# LEDs.net
KiCad netlist of a schematic drawn in Altium Designer
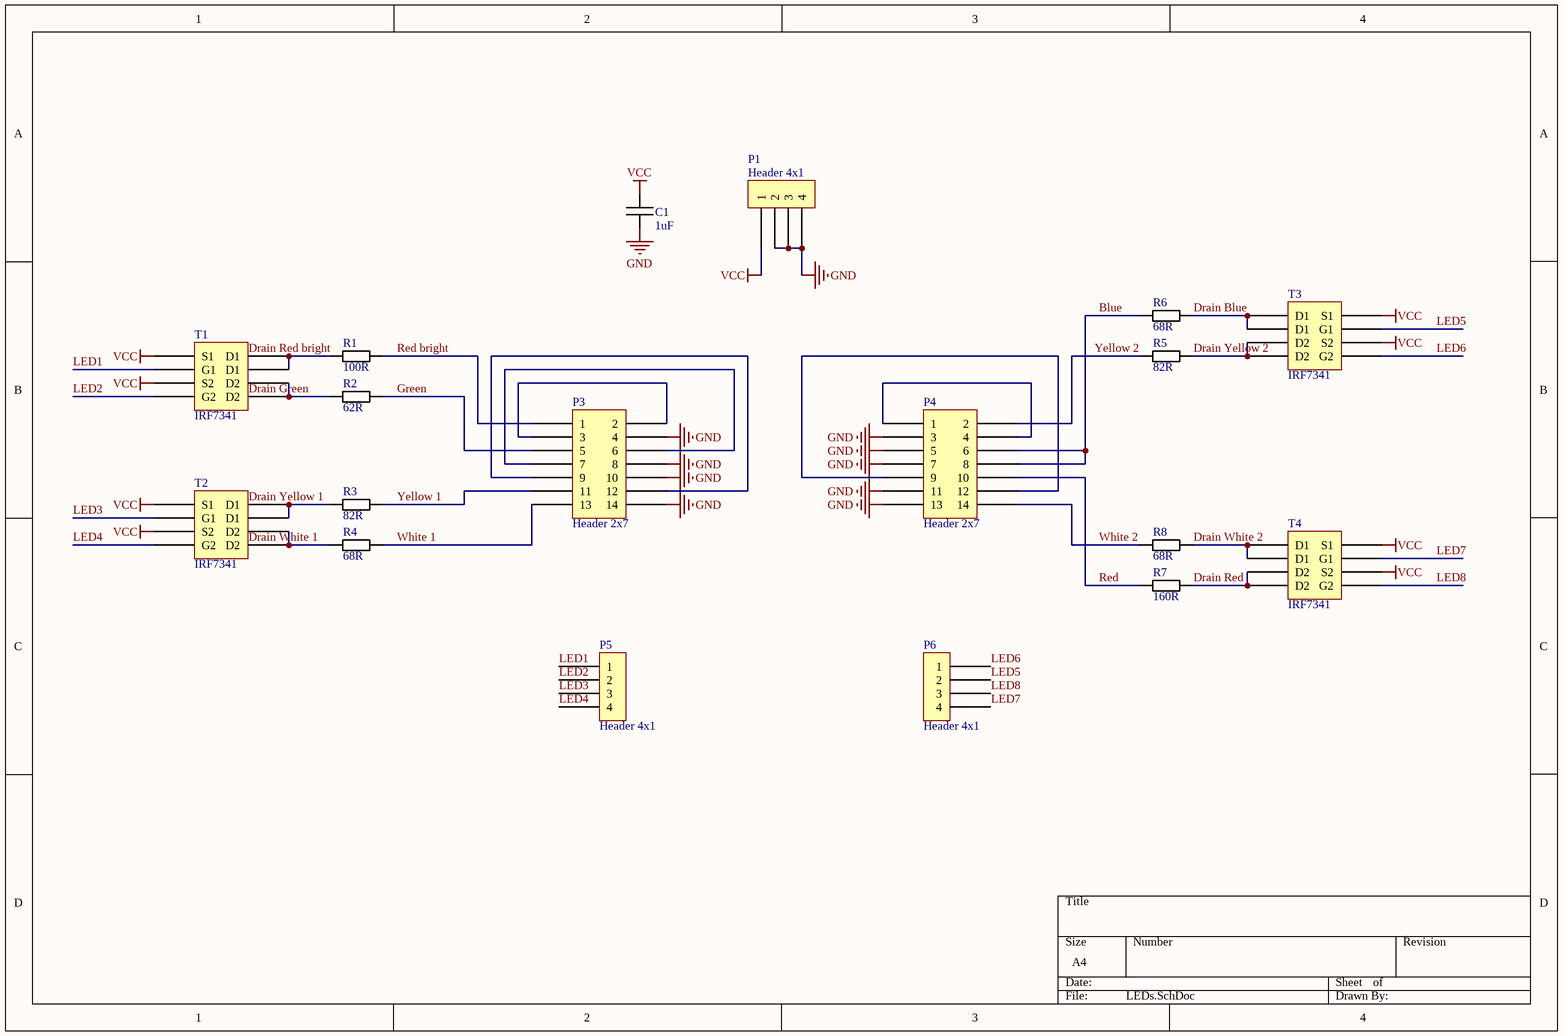
[diagram p0: LEDs.SchDoc]

(export (version "E")
  (design (tool "Eeschema 10.0.6"))
  (components
    (comp (ref "C1") (value "1uF") (footprint "C 0805 / 2012") (libsource (lib "LEDs") (part "Capacitor")))
    (comp (ref "P1")
      (value "Header 4x1")
      (footprint "Header 4x1 2.54mm")
      (libsource (lib "") (part "Header 4x1_1"))
    )
    (comp (ref "P3")
      (value "Header 2x7")
      (footprint "Header 7x2 2.54mm")
      (libsource (lib "LEDs") (part "Header 2x7"))
    )
    (comp (ref "P4")
      (value "Header 2x7")
      (footprint "Header 7x2 2.54mm")
      (libsource (lib "LEDs") (part "Header 2x7"))
    )
    (comp (ref "P5")
      (value "Header 4x1")
      (footprint "Header 4x1 2.54mm")
      (libsource (lib "LEDs") (part "Header 4x1"))
    )
    (comp (ref "P6")
      (value "Header 4x1")
      (footprint "Header 4x1 2.54mm")
      (libsource (lib "") (part "Header 4x1_2"))
    )
    (comp (ref "R1")
      (value "100R")
      (footprint "R 0805 / 2012")
      (description "Resistor")
      (libsource (lib "LEDs") (part "Resistor"))
    )
    (comp (ref "R2")
      (value "62R")
      (footprint "R 0805 / 2012")
      (description "Resistor")
      (libsource (lib "LEDs") (part "Resistor"))
    )
    (comp (ref "R3")
      (value "82R")
      (footprint "R 0805 / 2012")
      (description "Resistor")
      (libsource (lib "LEDs") (part "Resistor"))
    )
    (comp (ref "R4")
      (value "68R")
      (footprint "R 0805 / 2012")
      (description "Resistor")
      (libsource (lib "LEDs") (part "Resistor"))
    )
    (comp (ref "R5")
      (value "82R")
      (footprint "R 0805 / 2012")
      (description "Resistor")
      (libsource (lib "LEDs") (part "Resistor"))
    )
    (comp (ref "R6")
      (value "68R")
      (footprint "R 0805 / 2012")
      (description "Resistor")
      (libsource (lib "LEDs") (part "Resistor"))
    )
    (comp (ref "R7")
      (value "160R")
      (footprint "R 0805 / 2012")
      (description "Resistor")
      (libsource (lib "LEDs") (part "Resistor"))
    )
    (comp (ref "R8")
      (value "68R")
      (footprint "R 0805 / 2012")
      (description "Resistor")
      (libsource (lib "LEDs") (part "Resistor"))
    )
    (comp (ref "T1") (value "IRF7341") (footprint "SOIC8") (libsource (lib "") (part "IRF7341_1")))
    (comp (ref "T2") (value "IRF7341") (footprint "SOIC8") (libsource (lib "") (part "IRF7341_1")))
    (comp (ref "T3") (value "IRF7341") (footprint "SOIC8") (libsource (lib "LEDs") (part "IRF7341")))
    (comp (ref "T4") (value "IRF7341") (footprint "SOIC8") (libsource (lib "LEDs") (part "IRF7341")))
  )
  (nets
    (net (code "1") (name "/Blue") (class "Default")
      (node (ref "P4") (pin "6") (pinfunction "6_6") (pintype "passive"))
      (node (ref "P4") (pin "8") (pinfunction "8_8") (pintype "passive"))
      (node (ref "R6") (pin "1") (pinfunction "1_1") (pintype "passive"))
    )
    (net (code "2") (name "/Drain Blue") (class "Default")
      (node (ref "R6") (pin "2") (pinfunction "2_2") (pintype "passive"))
      (node (ref "T3") (pin "7") (pinfunction "D1_7") (pintype "passive"))
      (node (ref "T3") (pin "8") (pinfunction "D1_8") (pintype "passive"))
    )
    (net (code "4") (name "/Drain Red") (class "Default")
      (node (ref "R7") (pin "2") (pinfunction "2_2") (pintype "passive"))
      (node (ref "T4") (pin "5") (pinfunction "D2_5") (pintype "passive"))
      (node (ref "T4") (pin "6") (pinfunction "D2_6") (pintype "passive"))
    )
    (net (code "7") (name "/Drain White 2") (class "Default")
      (node (ref "R8") (pin "2") (pinfunction "2_2") (pintype "passive"))
      (node (ref "T4") (pin "7") (pinfunction "D1_7") (pintype "passive"))
      (node (ref "T4") (pin "8") (pinfunction "D1_8") (pintype "passive"))
    )
    (net (code "9") (name "/Drain Yellow 2") (class "Default")
      (node (ref "R5") (pin "2") (pinfunction "2_2") (pintype "passive"))
      (node (ref "T3") (pin "5") (pinfunction "D2_5") (pintype "passive"))
      (node (ref "T3") (pin "6") (pinfunction "D2_6") (pintype "passive"))
    )
    (net (code "10") (name "/Green") (class "Default")
      (node (ref "P3") (pin "5") (pinfunction "5_5") (pintype "passive"))
      (node (ref "R2") (pin "2") (pinfunction "2_2") (pintype "passive"))
    )
    (net (code "11") (name "/LED1") (class "Default")
      (node (ref "P5") (pin "1") (pinfunction "1_1") (pintype "passive"))
      (node (ref "T1") (pin "2") (pinfunction "G1_2") (pintype "passive"))
    )
    (net (code "12") (name "/LED2") (class "Default")
      (node (ref "P5") (pin "2") (pinfunction "2_2") (pintype "passive"))
      (node (ref "T1") (pin "4") (pinfunction "G2_4") (pintype "passive"))
    )
    (net (code "13") (name "/LED3") (class "Default")
      (node (ref "P5") (pin "3") (pinfunction "3_3") (pintype "passive"))
      (node (ref "T2") (pin "2") (pinfunction "G1_2") (pintype "passive"))
    )
    (net (code "14") (name "/LED4") (class "Default")
      (node (ref "P5") (pin "4") (pinfunction "4_4") (pintype "passive"))
      (node (ref "T2") (pin "4") (pinfunction "G2_4") (pintype "passive"))
    )
    (net (code "15") (name "/LED5") (class "Default")
      (node (ref "P6") (pin "2") (pinfunction "2_2") (pintype "passive"))
      (node (ref "T3") (pin "2") (pinfunction "G1_2") (pintype "passive"))
    )
    (net (code "16") (name "/LED6") (class "Default")
      (node (ref "P6") (pin "1") (pinfunction "1_1") (pintype "passive"))
      (node (ref "T3") (pin "4") (pinfunction "G2_4") (pintype "passive"))
    )
    (net (code "17") (name "/LED7") (class "Default")
      (node (ref "P6") (pin "4") (pinfunction "4_4") (pintype "passive"))
      (node (ref "T4") (pin "2") (pinfunction "G1_2") (pintype "passive"))
    )
    (net (code "18") (name "/LED8") (class "Default")
      (node (ref "P6") (pin "3") (pinfunction "3_3") (pintype "passive"))
      (node (ref "T4") (pin "4") (pinfunction "G2_4") (pintype "passive"))
    )
    (net (code "19") (name "/Red") (class "Default")
      (node (ref "P4") (pin "10") (pinfunction "10_10") (pintype "passive"))
      (node (ref "R7") (pin "1") (pinfunction "1_1") (pintype "passive"))
    )
    (net (code "20") (name "/Red bright") (class "Default")
      (node (ref "P3") (pin "1") (pinfunction "1_1") (pintype "passive"))
      (node (ref "R1") (pin "2") (pinfunction "2_2") (pintype "passive"))
    )
    (net (code "21") (name "/White 1") (class "Default")
      (node (ref "P3") (pin "13") (pinfunction "13_13") (pintype "passive"))
      (node (ref "R4") (pin "2") (pinfunction "2_2") (pintype "passive"))
    )
    (net (code "22") (name "/White 2") (class "Default")
      (node (ref "P4") (pin "14") (pinfunction "14_14") (pintype "passive"))
      (node (ref "R8") (pin "1") (pinfunction "1_1") (pintype "passive"))
    )
    (net (code "23") (name "/Yellow 1") (class "Default")
      (node (ref "P3") (pin "11") (pinfunction "11_11") (pintype "passive"))
      (node (ref "R3") (pin "2") (pinfunction "2_2") (pintype "passive"))
    )
    (net (code "24") (name "/Yellow 2") (class "Default")
      (node (ref "P4") (pin "2") (pinfunction "2_2") (pintype "passive"))
      (node (ref "R5") (pin "1") (pinfunction "1_1") (pintype "passive"))
    )
    (net (code "25") (name "GND") (class "Default")
      (node (ref "C1") (pin "2") (pinfunction "1_2") (pintype "passive"))
      (node (ref "P1") (pin "2") (pinfunction "2_2") (pintype "passive"))
      (node (ref "P1") (pin "3") (pinfunction "3_3") (pintype "passive"))
      (node (ref "P1") (pin "4") (pinfunction "4_4") (pintype "passive"))
      (node (ref "P3") (pin "10") (pinfunction "10_10") (pintype "passive"))
      (node (ref "P3") (pin "14") (pinfunction "14_14") (pintype "passive"))
      (node (ref "P3") (pin "4") (pinfunction "4_4") (pintype "passive"))
      (node (ref "P3") (pin "8") (pinfunction "8_8") (pintype "passive"))
      (node (ref "P4") (pin "11") (pinfunction "11_11") (pintype "passive"))
      (node (ref "P4") (pin "13") (pinfunction "13_13") (pintype "passive"))
      (node (ref "P4") (pin "3") (pinfunction "3_3") (pintype "passive"))
      (node (ref "P4") (pin "5") (pinfunction "5_5") (pintype "passive"))
      (node (ref "P4") (pin "7") (pinfunction "7_7") (pintype "passive"))
    )
    (net (code "26") (name "Net-(P3-Pad2)") (class "Default")
      (node (ref "P3") (pin "2") (pinfunction "2_2") (pintype "passive"))
      (node (ref "P3") (pin "3") (pinfunction "3_3") (pintype "passive"))
    )
    (net (code "27") (name "Net-(P3-Pad6)") (class "Default")
      (node (ref "P3") (pin "6") (pinfunction "6_6") (pintype "passive"))
      (node (ref "P3") (pin "7") (pinfunction "7_7") (pintype "passive"))
    )
    (net (code "28") (name "Net-(P3-Pad12)") (class "Default")
      (node (ref "P3") (pin "12") (pinfunction "12_12") (pintype "passive"))
      (node (ref "P3") (pin "9") (pinfunction "9_9") (pintype "passive"))
    )
    (net (code "29") (name "Net-(P4-Pad1)") (class "Default")
      (node (ref "P4") (pin "1") (pinfunction "1_1") (pintype "passive"))
      (node (ref "P4") (pin "4") (pinfunction "4_4") (pintype "passive"))
    )
    (net (code "30") (name "Net-(P4-Pad12)") (class "Default")
      (node (ref "P4") (pin "12") (pinfunction "12_12") (pintype "passive"))
      (node (ref "P4") (pin "9") (pinfunction "9_9") (pintype "passive"))
    )
    (net (code "31") (name "Net-(R1-Pad1)") (class "Default")
      (node (ref "R1") (pin "1") (pinfunction "1_1") (pintype "passive"))
      (node (ref "T1") (pin "7") (pinfunction "D1_7") (pintype "passive"))
      (node (ref "T1") (pin "8") (pinfunction "D1_8") (pintype "passive"))
    )
    (net (code "32") (name "Net-(R2-Pad1)") (class "Default")
      (node (ref "R2") (pin "1") (pinfunction "1_1") (pintype "passive"))
      (node (ref "T1") (pin "5") (pinfunction "D2_5") (pintype "passive"))
      (node (ref "T1") (pin "6") (pinfunction "D2_6") (pintype "passive"))
    )
    (net (code "33") (name "Net-(R3-Pad1)") (class "Default")
      (node (ref "R3") (pin "1") (pinfunction "1_1") (pintype "passive"))
      (node (ref "T2") (pin "7") (pinfunction "D1_7") (pintype "passive"))
      (node (ref "T2") (pin "8") (pinfunction "D1_8") (pintype "passive"))
    )
    (net (code "34") (name "Net-(R4-Pad1)") (class "Default")
      (node (ref "R4") (pin "1") (pinfunction "1_1") (pintype "passive"))
      (node (ref "T2") (pin "5") (pinfunction "D2_5") (pintype "passive"))
      (node (ref "T2") (pin "6") (pinfunction "D2_6") (pintype "passive"))
    )
    (net (code "35") (name "VCC") (class "Default")
      (node (ref "C1") (pin "1") (pinfunction "1_1") (pintype "passive"))
      (node (ref "P1") (pin "1") (pinfunction "1_1") (pintype "passive"))
      (node (ref "T1") (pin "1") (pinfunction "S1_1") (pintype "passive"))
      (node (ref "T1") (pin "3") (pinfunction "S2_3") (pintype "passive"))
      (node (ref "T2") (pin "1") (pinfunction "S1_1") (pintype "passive"))
      (node (ref "T2") (pin "3") (pinfunction "S2_3") (pintype "passive"))
      (node (ref "T3") (pin "1") (pinfunction "S1_1") (pintype "passive"))
      (node (ref "T3") (pin "3") (pinfunction "S2_3") (pintype "passive"))
      (node (ref "T4") (pin "1") (pinfunction "S1_1") (pintype "passive"))
      (node (ref "T4") (pin "3") (pinfunction "S2_3") (pintype "passive"))
    )
  )
)
